# ORing_block.net
KiCad netlist of a schematic drawn in EAGLE
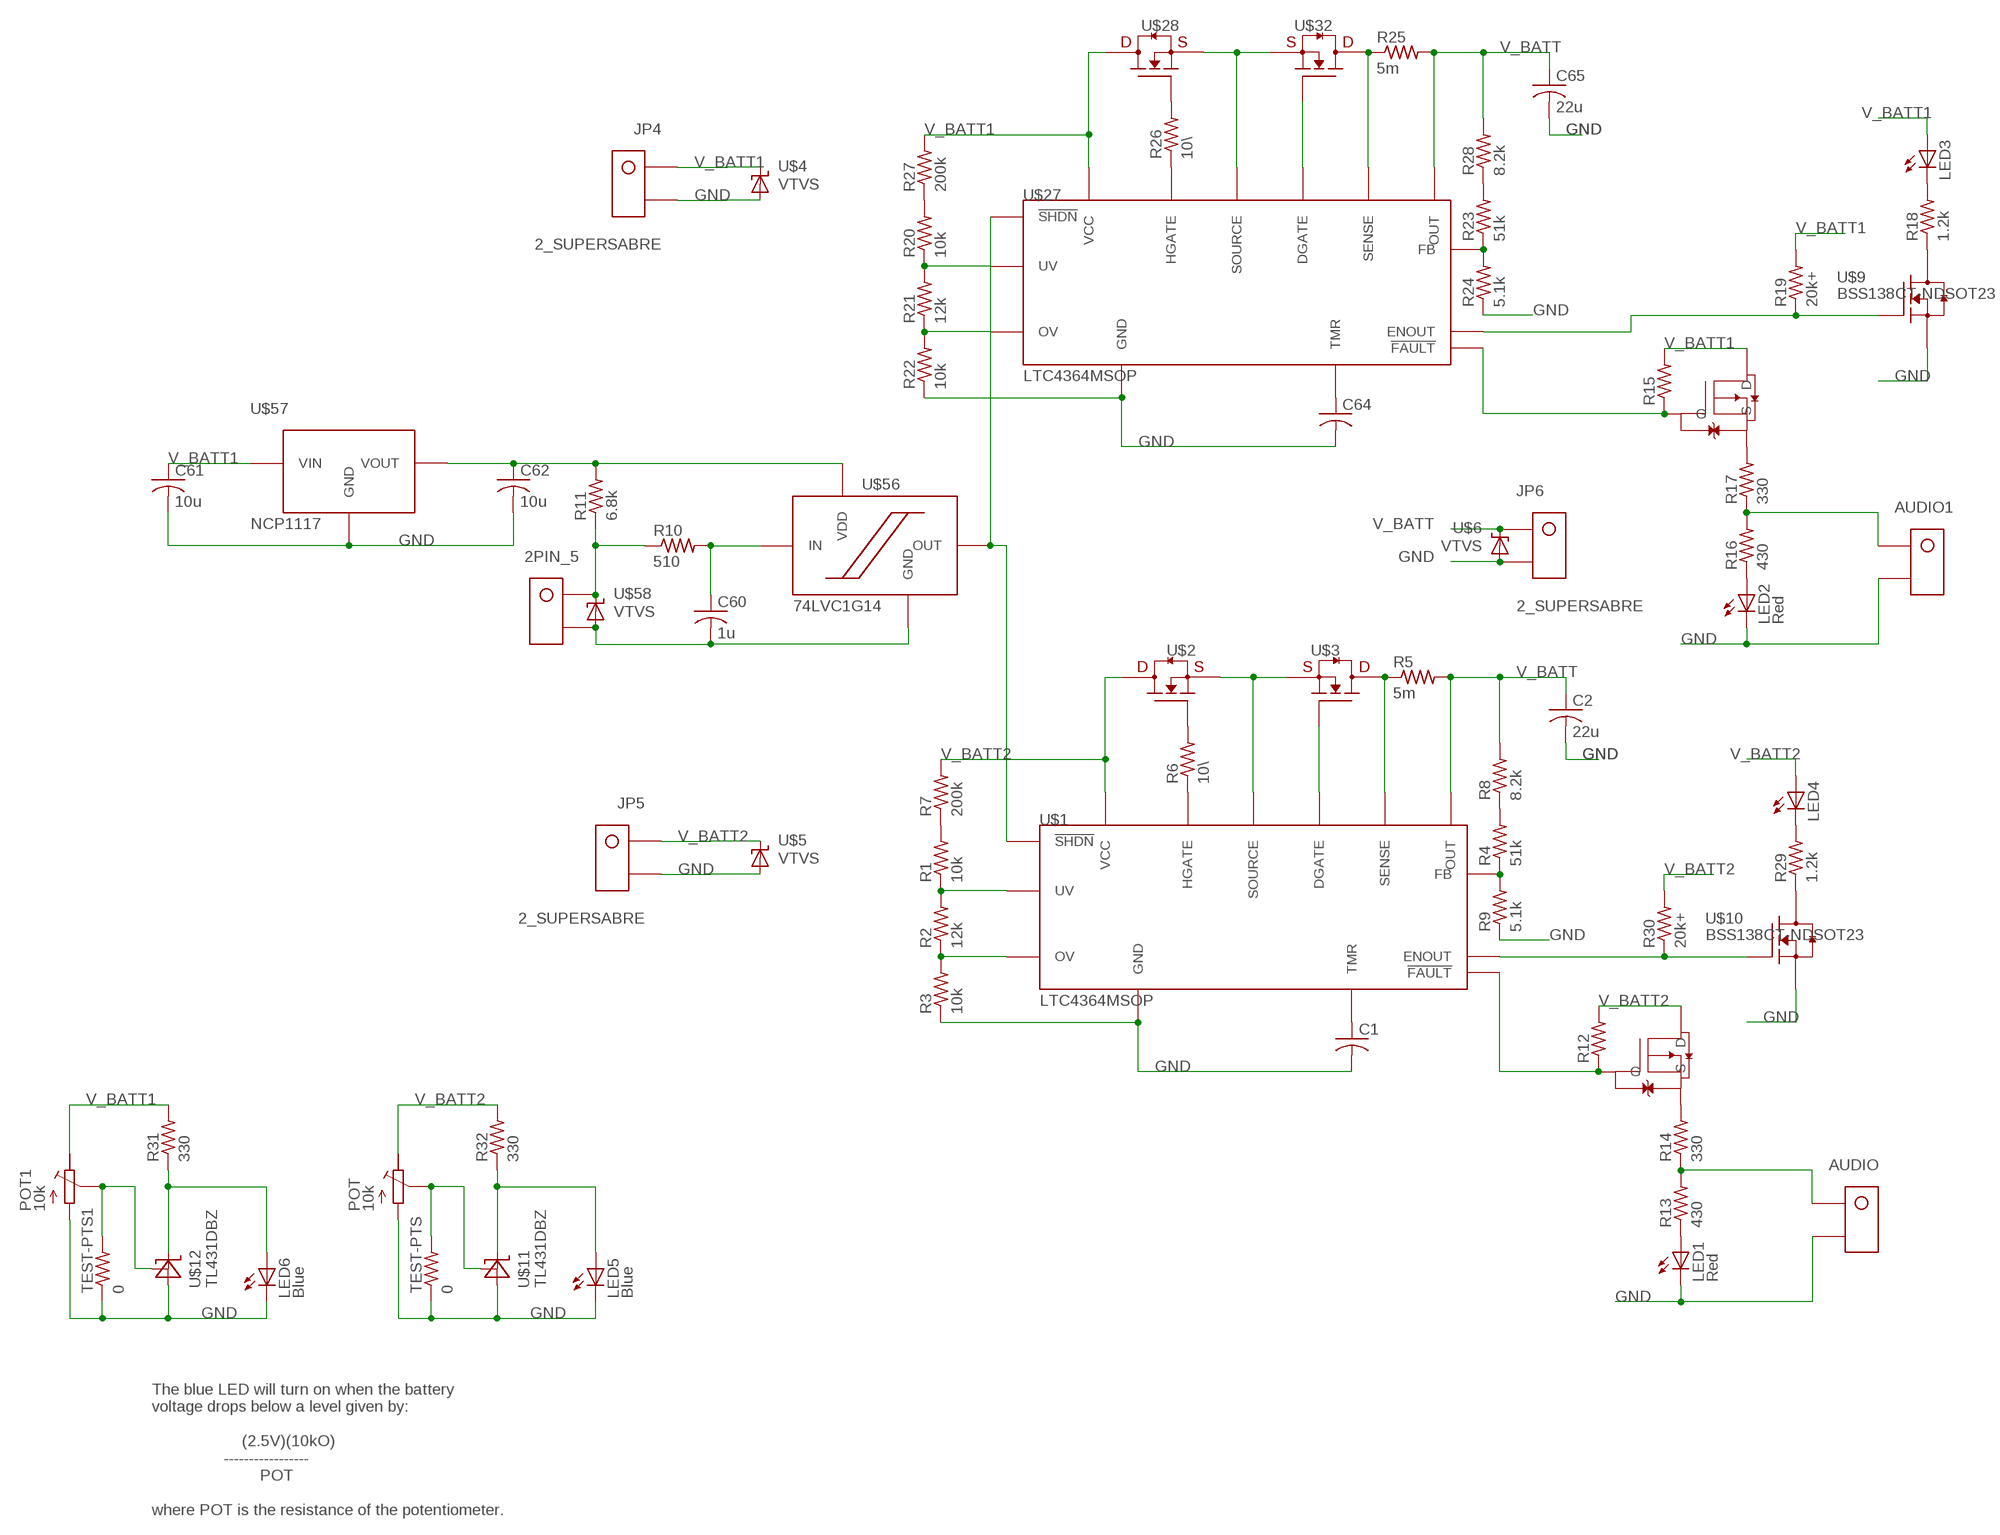
[diagram p0: schematic, sheet 1]

(export (version "E")
  (design (tool "Eeschema 10.0.6"))
  (components
    (comp (ref "2PIN_5")
      (value "KK254_VERT_2PIN22-29-2021")
      (footprint "eagle-import:KK254_VERT_2PIN")
      (libsource (lib "eagle-import") (part "KK254_VERT_2PIN22-29-2021"))
    )
    (comp (ref "AUDIO")
      (value "KK254_VERT_2PIN22-29-2021")
      (footprint "eagle-import:KK254_VERT_2PIN")
      (libsource (lib "eagle-import") (part "KK254_VERT_2PIN22-29-2021"))
    )
    (comp (ref "AUDIO1")
      (value "KK254_VERT_2PIN22-29-2021")
      (footprint "eagle-import:KK254_VERT_2PIN")
      (libsource (lib "eagle-import") (part "KK254_VERT_2PIN22-29-2021"))
    )
    (comp (ref "C1")
      (value "C-USC0805")
      (footprint "eagle-import:C0805")
      (libsource (lib "eagle-import") (part "C-USC0805"))
    )
    (comp (ref "C2")
      (value "22u")
      (footprint "eagle-import:C0805")
      (libsource (lib "eagle-import") (part "C-USC0805"))
    )
    (comp (ref "C60")
      (value "1u")
      (footprint "eagle-import:C0805")
      (libsource (lib "eagle-import") (part "C-USC0805"))
    )
    (comp (ref "C61")
      (value "10u")
      (footprint "eagle-import:C0805")
      (libsource (lib "eagle-import") (part "C-USC0805"))
    )
    (comp (ref "C62")
      (value "10u")
      (footprint "eagle-import:C0805")
      (libsource (lib "eagle-import") (part "C-USC0805"))
    )
    (comp (ref "C64")
      (value "C-USC0805")
      (footprint "eagle-import:C0805")
      (libsource (lib "eagle-import") (part "C-USC0805"))
    )
    (comp (ref "C65")
      (value "22u")
      (footprint "eagle-import:C0805")
      (libsource (lib "eagle-import") (part "C-USC0805"))
    )
    (comp (ref "JP4")
      (value "2_SUPERSABRE")
      (footprint "eagle-import:SUPERSABRE_2CIRCUIT")
      (libsource (lib "eagle-import") (part "2_SUPERSABRE"))
    )
    (comp (ref "JP5")
      (value "2_SUPERSABRE")
      (footprint "eagle-import:SUPERSABRE_2CIRCUIT")
      (libsource (lib "eagle-import") (part "2_SUPERSABRE"))
    )
    (comp (ref "JP6")
      (value "2_SUPERSABRE")
      (footprint "eagle-import:SUPERSABRE_2CIRCUIT")
      (libsource (lib "eagle-import") (part "2_SUPERSABRE"))
    )
    (comp (ref "LED1")
      (value "Red")
      (footprint "eagle-import:CHIPLED_0805")
      (libsource (lib "eagle-import") (part "LEDCHIPLED_0805"))
    )
    (comp (ref "LED2")
      (value "Red")
      (footprint "eagle-import:CHIPLED_0805")
      (libsource (lib "eagle-import") (part "LEDCHIPLED_0805"))
    )
    (comp (ref "LED3")
      (value "LEDCHIPLED_0805")
      (footprint "eagle-import:CHIPLED_0805")
      (libsource (lib "eagle-import") (part "LEDCHIPLED_0805"))
    )
    (comp (ref "LED4")
      (value "LEDCHIPLED_0805")
      (footprint "eagle-import:CHIPLED_0805")
      (libsource (lib "eagle-import") (part "LEDCHIPLED_0805"))
    )
    (comp (ref "LED5")
      (value "Blue")
      (footprint "eagle-import:0805")
      (libsource (lib "eagle-import") (part "0805_LED"))
    )
    (comp (ref "LED6")
      (value "Blue")
      (footprint "eagle-import:0805")
      (libsource (lib "eagle-import") (part "0805_LED"))
    )
    (comp (ref "POT")
      (value "10k")
      (footprint "eagle-import:PTV09A-4")
      (libsource (lib "eagle-import") (part "R-TRIMMPTV09A-4"))
    )
    (comp (ref "POT1")
      (value "10k")
      (footprint "eagle-import:PTV09A-4")
      (libsource (lib "eagle-import") (part "R-TRIMMPTV09A-4"))
    )
    (comp (ref "R1")
      (value "10k")
      (footprint "eagle-import:R0805")
      (libsource (lib "eagle-import") (part "R-US_R0805"))
    )
    (comp (ref "R2")
      (value "12k")
      (footprint "eagle-import:R0805")
      (libsource (lib "eagle-import") (part "R-US_R0805"))
    )
    (comp (ref "R3")
      (value "10k")
      (footprint "eagle-import:R0805")
      (libsource (lib "eagle-import") (part "R-US_R0805"))
    )
    (comp (ref "R4")
      (value "51k")
      (footprint "eagle-import:R0805")
      (libsource (lib "eagle-import") (part "R-US_R0805"))
    )
    (comp (ref "R5")
      (value "5m")
      (footprint "eagle-import:R0805")
      (libsource (lib "eagle-import") (part "R-US_R0805"))
    )
    (comp (ref "R6")
      (value "10\\")
      (footprint "eagle-import:R0805")
      (libsource (lib "eagle-import") (part "R-US_R0805"))
    )
    (comp (ref "R7")
      (value "200k")
      (footprint "eagle-import:R0805")
      (libsource (lib "eagle-import") (part "R-US_R0805"))
    )
    (comp (ref "R8")
      (value "8.2k")
      (footprint "eagle-import:R0805")
      (libsource (lib "eagle-import") (part "R-US_R0805"))
    )
    (comp (ref "R9")
      (value "5.1k")
      (footprint "eagle-import:R0805")
      (libsource (lib "eagle-import") (part "R-US_R0805"))
    )
    (comp (ref "R10")
      (value "510")
      (footprint "eagle-import:R0805")
      (libsource (lib "eagle-import") (part "R-US_R0805"))
    )
    (comp (ref "R11")
      (value "6.8k")
      (footprint "eagle-import:R0805")
      (libsource (lib "eagle-import") (part "R-US_R0805"))
    )
    (comp (ref "R12")
      (value "R-US_R0805")
      (footprint "eagle-import:R0805")
      (libsource (lib "eagle-import") (part "R-US_R0805"))
    )
    (comp (ref "R13")
      (value "430")
      (footprint "eagle-import:R0805")
      (libsource (lib "eagle-import") (part "R-US_R0805"))
    )
    (comp (ref "R14")
      (value "330")
      (footprint "eagle-import:R0805")
      (libsource (lib "eagle-import") (part "R-US_R0805"))
    )
    (comp (ref "R15")
      (value "R-US_R0805")
      (footprint "eagle-import:R0805")
      (libsource (lib "eagle-import") (part "R-US_R0805"))
    )
    (comp (ref "R16")
      (value "430")
      (footprint "eagle-import:R0805")
      (libsource (lib "eagle-import") (part "R-US_R0805"))
    )
    (comp (ref "R17")
      (value "330")
      (footprint "eagle-import:R0805")
      (libsource (lib "eagle-import") (part "R-US_R0805"))
    )
    (comp (ref "R18")
      (value "1.2k")
      (footprint "eagle-import:R0805")
      (libsource (lib "eagle-import") (part "R-US_R0805"))
    )
    (comp (ref "R19")
      (value "20k+")
      (footprint "eagle-import:R0805")
      (libsource (lib "eagle-import") (part "R-US_R0805"))
    )
    (comp (ref "R20")
      (value "10k")
      (footprint "eagle-import:R0805")
      (libsource (lib "eagle-import") (part "R-US_R0805"))
    )
    (comp (ref "R21")
      (value "12k")
      (footprint "eagle-import:R0805")
      (libsource (lib "eagle-import") (part "R-US_R0805"))
    )
    (comp (ref "R22")
      (value "10k")
      (footprint "eagle-import:R0805")
      (libsource (lib "eagle-import") (part "R-US_R0805"))
    )
    (comp (ref "R23")
      (value "51k")
      (footprint "eagle-import:R0805")
      (libsource (lib "eagle-import") (part "R-US_R0805"))
    )
    (comp (ref "R24")
      (value "5.1k")
      (footprint "eagle-import:R0805")
      (libsource (lib "eagle-import") (part "R-US_R0805"))
    )
    (comp (ref "R25")
      (value "5m")
      (footprint "eagle-import:R0805")
      (libsource (lib "eagle-import") (part "R-US_R0805"))
    )
    (comp (ref "R26")
      (value "10\\")
      (footprint "eagle-import:R0805")
      (libsource (lib "eagle-import") (part "R-US_R0805"))
    )
    (comp (ref "R27")
      (value "200k")
      (footprint "eagle-import:R0805")
      (libsource (lib "eagle-import") (part "R-US_R0805"))
    )
    (comp (ref "R28")
      (value "8.2k")
      (footprint "eagle-import:R0805")
      (libsource (lib "eagle-import") (part "R-US_R0805"))
    )
    (comp (ref "R29")
      (value "1.2k")
      (footprint "eagle-import:R0805")
      (libsource (lib "eagle-import") (part "R-US_R0805"))
    )
    (comp (ref "R30")
      (value "20k+")
      (footprint "eagle-import:R0805")
      (libsource (lib "eagle-import") (part "R-US_R0805"))
    )
    (comp (ref "R31")
      (value "330")
      (footprint "eagle-import:R0805")
      (libsource (lib "eagle-import") (part "R-US_R0805"))
    )
    (comp (ref "R32")
      (value "330")
      (footprint "eagle-import:R0805")
      (libsource (lib "eagle-import") (part "R-US_R0805"))
    )
    (comp (ref "TEST-PTS")
      (value "0")
      (footprint "eagle-import:V526-0")
      (libsource (lib "eagle-import") (part "R-US_V526-0"))
    )
    (comp (ref "TEST-PTS1")
      (value "0")
      (footprint "eagle-import:V526-0")
      (libsource (lib "eagle-import") (part "R-US_V526-0"))
    )
    (comp (ref "U$1")
      (value "LTC4364MSOP")
      (footprint "eagle-import:MSOP16")
      (libsource (lib "eagle-import") (part "LTC4364MSOP"))
    )
    (comp (ref "U$2")
      (value "FDMC8360LET40PWR33")
      (footprint "eagle-import:POWER33")
      (libsource (lib "eagle-import") (part "FDMC8360LET40PWR33"))
    )
    (comp (ref "U$3")
      (value "FDMC8360LET40PWR33")
      (footprint "eagle-import:POWER33")
      (libsource (lib "eagle-import") (part "FDMC8360LET40PWR33"))
    )
    (comp (ref "U$4")
      (value "VTVS")
      (footprint "eagle-import:DO-219AB")
      (libsource (lib "eagle-import") (part "VTVS"))
    )
    (comp (ref "U$5")
      (value "VTVS")
      (footprint "eagle-import:DO-219AB")
      (libsource (lib "eagle-import") (part "VTVS"))
    )
    (comp (ref "U$6")
      (value "VTVS")
      (footprint "eagle-import:DO-219AB")
      (libsource (lib "eagle-import") (part "VTVS"))
    )
    (comp (ref "U$7")
      (value "DMP32D5SFB")
      (footprint "eagle-import:AP02002")
      (libsource (lib "eagle-import") (part "DMP32D5SFB"))
    )
    (comp (ref "U$8")
      (value "DMP32D5SFB")
      (footprint "eagle-import:AP02002")
      (libsource (lib "eagle-import") (part "DMP32D5SFB"))
    )
    (comp (ref "U$9")
      (value "BSS138CT-NDSOT23")
      (footprint "eagle-import:SOT23")
      (libsource (lib "eagle-import") (part "BSS138CT-NDSOT23"))
    )
    (comp (ref "U$10")
      (value "BSS138CT-NDSOT23")
      (footprint "eagle-import:SOT23")
      (libsource (lib "eagle-import") (part "BSS138CT-NDSOT23"))
    )
    (comp (ref "U$11")
      (value "TL431DBZ")
      (footprint "eagle-import:SOT-23-3")
      (libsource (lib "eagle-import") (part "TL431DBZ"))
    )
    (comp (ref "U$12")
      (value "TL431DBZ")
      (footprint "eagle-import:SOT-23-3")
      (libsource (lib "eagle-import") (part "TL431DBZ"))
    )
    (comp (ref "U$27")
      (value "LTC4364MSOP")
      (footprint "eagle-import:MSOP16")
      (libsource (lib "eagle-import") (part "LTC4364MSOP"))
    )
    (comp (ref "U$28")
      (value "FDMC8360LET40PWR33")
      (footprint "eagle-import:POWER33")
      (libsource (lib "eagle-import") (part "FDMC8360LET40PWR33"))
    )
    (comp (ref "U$32")
      (value "FDMC8360LET40PWR33")
      (footprint "eagle-import:POWER33")
      (libsource (lib "eagle-import") (part "FDMC8360LET40PWR33"))
    )
    (comp (ref "U$56")
      (value "74LVC1G14")
      (footprint "eagle-import:TSSOP5")
      (libsource (lib "eagle-import") (part "74LVC1G14"))
    )
    (comp (ref "U$57")
      (value "NCP1117")
      (footprint "eagle-import:SOT-223")
      (libsource (lib "eagle-import") (part "NCP1117"))
    )
    (comp (ref "U$58")
      (value "VTVS")
      (footprint "eagle-import:DO-219AB")
      (libsource (lib "eagle-import") (part "VTVS"))
    )
  )
  (nets
    (net (code "1") (name "/GND") (class "Default")
      (node (ref "AUDIO") (pin "P$2") (pinfunction "P$2_P$2") (pintype "bidirectional"))
      (node (ref "AUDIO1") (pin "P$2") (pinfunction "P$2_P$2") (pintype "bidirectional"))
      (node (ref "C1") (pin "2") (pinfunction "2_2") (pintype "passive"))
      (node (ref "C2") (pin "2") (pinfunction "2_2") (pintype "passive"))
      (node (ref "C61") (pin "2") (pinfunction "2_2") (pintype "passive"))
      (node (ref "C62") (pin "2") (pinfunction "2_2") (pintype "passive"))
      (node (ref "C64") (pin "2") (pinfunction "2_2") (pintype "passive"))
      (node (ref "C65") (pin "2") (pinfunction "2_2") (pintype "passive"))
      (node (ref "JP4") (pin "P$2") (pinfunction "P$2_P$2") (pintype "bidirectional"))
      (node (ref "JP5") (pin "P$2") (pinfunction "P$2_P$2") (pintype "bidirectional"))
      (node (ref "JP6") (pin "P$2") (pinfunction "P$2_P$2") (pintype "bidirectional"))
      (node (ref "LED1") (pin "C") (pinfunction "C_C") (pintype "passive"))
      (node (ref "LED2") (pin "C") (pinfunction "C_C") (pintype "passive"))
      (node (ref "LED5") (pin "P$2") (pinfunction "C_P$2") (pintype "passive"))
      (node (ref "LED6") (pin "P$2") (pinfunction "C_P$2") (pintype "passive"))
      (node (ref "POT") (pin "P$3") (pinfunction "E_P$3") (pintype "passive"))
      (node (ref "POT1") (pin "P$3") (pinfunction "E_P$3") (pintype "passive"))
      (node (ref "R22") (pin "1") (pinfunction "1_1") (pintype "passive"))
      (node (ref "R24") (pin "1") (pinfunction "1_1") (pintype "passive"))
      (node (ref "R3") (pin "1") (pinfunction "1_1") (pintype "passive"))
      (node (ref "R9") (pin "1") (pinfunction "1_1") (pintype "passive"))
      (node (ref "TEST-PTS") (pin "1") (pinfunction "1_1") (pintype "passive"))
      (node (ref "TEST-PTS1") (pin "1") (pinfunction "1_1") (pintype "passive"))
      (node (ref "U$1") (pin "GND") (pinfunction "GND_GND") (pintype "bidirectional"))
      (node (ref "U$10") (pin "2") (pinfunction "S_2") (pintype "passive"))
      (node (ref "U$11") (pin "P$3") (pinfunction "A_P$3") (pintype "passive"))
      (node (ref "U$12") (pin "P$3") (pinfunction "A_P$3") (pintype "passive"))
      (node (ref "U$27") (pin "GND") (pinfunction "GND_GND") (pintype "bidirectional"))
      (node (ref "U$4") (pin "P$1") (pinfunction "A_P$1") (pintype "passive"))
      (node (ref "U$5") (pin "P$1") (pinfunction "A_P$1") (pintype "passive"))
      (node (ref "U$57") (pin "P$1") (pinfunction "GND_P$1") (pintype "bidirectional"))
      (node (ref "U$6") (pin "P$1") (pinfunction "A_P$1") (pintype "passive"))
      (node (ref "U$9") (pin "2") (pinfunction "S_2") (pintype "passive"))
    )
    (net (code "2") (name "/V_BATT") (class "Default")
      (node (ref "C2") (pin "1") (pinfunction "1_1") (pintype "passive"))
      (node (ref "C65") (pin "1") (pinfunction "1_1") (pintype "passive"))
      (node (ref "JP6") (pin "P$1") (pinfunction "P$1_P$1") (pintype "bidirectional"))
      (node (ref "R25") (pin "2") (pinfunction "2_2") (pintype "passive"))
      (node (ref "R28") (pin "2") (pinfunction "2_2") (pintype "passive"))
      (node (ref "R5") (pin "2") (pinfunction "2_2") (pintype "passive"))
      (node (ref "R8") (pin "2") (pinfunction "2_2") (pintype "passive"))
      (node (ref "U$1") (pin "OUT") (pinfunction "OUT_OUT") (pintype "bidirectional"))
      (node (ref "U$27") (pin "OUT") (pinfunction "OUT_OUT") (pintype "bidirectional"))
      (node (ref "U$6") (pin "P$2") (pinfunction "C_P$2") (pintype "passive"))
    )
    (net (code "3") (name "/V_BATT1") (class "Default")
      (node (ref "C61") (pin "1") (pinfunction "1_1") (pintype "passive"))
      (node (ref "JP4") (pin "P$1") (pinfunction "P$1_P$1") (pintype "bidirectional"))
      (node (ref "LED3") (pin "A") (pinfunction "A_A") (pintype "passive"))
      (node (ref "POT1") (pin "P$1") (pinfunction "A_P$1") (pintype "passive"))
      (node (ref "R15") (pin "2") (pinfunction "2_2") (pintype "passive"))
      (node (ref "R19") (pin "2") (pinfunction "2_2") (pintype "passive"))
      (node (ref "R27") (pin "2") (pinfunction "2_2") (pintype "passive"))
      (node (ref "R31") (pin "2") (pinfunction "2_2") (pintype "passive"))
      (node (ref "U$27") (pin "VCC") (pinfunction "VCC_VCC") (pintype "bidirectional"))
      (node (ref "U$28") (pin "DRAIN") (pinfunction "DRAIN_DRAIN") (pintype "bidirectional"))
      (node (ref "U$4") (pin "P$2") (pinfunction "C_P$2") (pintype "passive"))
      (node (ref "U$57") (pin "P$3") (pinfunction "VIN_P$3") (pintype "bidirectional"))
      (node (ref "U$8") (pin "P$3") (pinfunction "D_P$3") (pintype "bidirectional"))
    )
    (net (code "4") (name "/V_BATT2") (class "Default")
      (node (ref "JP5") (pin "P$1") (pinfunction "P$1_P$1") (pintype "bidirectional"))
      (node (ref "LED4") (pin "A") (pinfunction "A_A") (pintype "passive"))
      (node (ref "POT") (pin "P$1") (pinfunction "A_P$1") (pintype "passive"))
      (node (ref "R12") (pin "2") (pinfunction "2_2") (pintype "passive"))
      (node (ref "R30") (pin "2") (pinfunction "2_2") (pintype "passive"))
      (node (ref "R32") (pin "2") (pinfunction "2_2") (pintype "passive"))
      (node (ref "R7") (pin "2") (pinfunction "2_2") (pintype "passive"))
      (node (ref "U$1") (pin "VCC") (pinfunction "VCC_VCC") (pintype "bidirectional"))
      (node (ref "U$2") (pin "DRAIN") (pinfunction "DRAIN_DRAIN") (pintype "bidirectional"))
      (node (ref "U$5") (pin "P$2") (pinfunction "C_P$2") (pintype "passive"))
      (node (ref "U$7") (pin "P$3") (pinfunction "D_P$3") (pintype "bidirectional"))
    )
    (net (code "5") (name "Net-(AUDIO-PadP$1)") (class "Default")
      (node (ref "AUDIO") (pin "P$1") (pinfunction "P$1_P$1") (pintype "bidirectional"))
      (node (ref "R13") (pin "2") (pinfunction "2_2") (pintype "passive"))
      (node (ref "R14") (pin "1") (pinfunction "1_1") (pintype "passive"))
    )
    (net (code "6") (name "Net-(AUDIO1-PadP$1)") (class "Default")
      (node (ref "AUDIO1") (pin "P$1") (pinfunction "P$1_P$1") (pintype "bidirectional"))
      (node (ref "R16") (pin "2") (pinfunction "2_2") (pintype "passive"))
      (node (ref "R17") (pin "1") (pinfunction "1_1") (pintype "passive"))
    )
    (net (code "7") (name "Net-(C1-Pad1)") (class "Default")
      (node (ref "C1") (pin "1") (pinfunction "1_1") (pintype "passive"))
      (node (ref "U$1") (pin "TMR") (pinfunction "TMR_TMR") (pintype "bidirectional"))
    )
    (net (code "8") (name "Net-(C64-Pad1)") (class "Default")
      (node (ref "C64") (pin "1") (pinfunction "1_1") (pintype "passive"))
      (node (ref "U$27") (pin "TMR") (pinfunction "TMR_TMR") (pintype "bidirectional"))
    )
    (net (code "9") (name "Net-(LED1-PadA)") (class "Default")
      (node (ref "LED1") (pin "A") (pinfunction "A_A") (pintype "passive"))
      (node (ref "R13") (pin "1") (pinfunction "1_1") (pintype "passive"))
    )
    (net (code "10") (name "Net-(LED2-PadA)") (class "Default")
      (node (ref "LED2") (pin "A") (pinfunction "A_A") (pintype "passive"))
      (node (ref "R16") (pin "1") (pinfunction "1_1") (pintype "passive"))
    )
    (net (code "11") (name "Net-(LED3-PadC)") (class "Default")
      (node (ref "LED3") (pin "C") (pinfunction "C_C") (pintype "passive"))
      (node (ref "R18") (pin "2") (pinfunction "2_2") (pintype "passive"))
    )
    (net (code "12") (name "Net-(LED4-PadC)") (class "Default")
      (node (ref "LED4") (pin "C") (pinfunction "C_C") (pintype "passive"))
      (node (ref "R29") (pin "2") (pinfunction "2_2") (pintype "passive"))
    )
    (net (code "13") (name "Net-(LED5-A)") (class "Default")
      (node (ref "LED5") (pin "P$1") (pinfunction "A_P$1") (pintype "passive"))
      (node (ref "R32") (pin "1") (pinfunction "1_1") (pintype "passive"))
      (node (ref "U$11") (pin "P$1") (pinfunction "C_P$1") (pintype "passive"))
    )
    (net (code "14") (name "Net-(LED6-A)") (class "Default")
      (node (ref "LED6") (pin "P$1") (pinfunction "A_P$1") (pintype "passive"))
      (node (ref "R31") (pin "1") (pinfunction "1_1") (pintype "passive"))
      (node (ref "U$12") (pin "P$1") (pinfunction "C_P$1") (pintype "passive"))
    )
    (net (code "15") (name "Net-(POT-S)") (class "Default")
      (node (ref "POT") (pin "P$2") (pinfunction "S_P$2") (pintype "passive"))
      (node (ref "TEST-PTS") (pin "2") (pinfunction "2_2") (pintype "passive"))
      (node (ref "U$11") (pin "P$2") (pinfunction "REF_P$2") (pintype "bidirectional"))
    )
    (net (code "16") (name "Net-(POT1-S)") (class "Default")
      (node (ref "POT1") (pin "P$2") (pinfunction "S_P$2") (pintype "passive"))
      (node (ref "TEST-PTS1") (pin "2") (pinfunction "2_2") (pintype "passive"))
      (node (ref "U$12") (pin "P$2") (pinfunction "REF_P$2") (pintype "bidirectional"))
    )
    (net (code "17") (name "Net-(R1-Pad1)") (class "Default")
      (node (ref "R1") (pin "1") (pinfunction "1_1") (pintype "passive"))
      (node (ref "R2") (pin "2") (pinfunction "2_2") (pintype "passive"))
      (node (ref "U$1") (pin "UV") (pinfunction "UV_UV") (pintype "bidirectional"))
    )
    (net (code "18") (name "Net-(R1-Pad2)") (class "Default")
      (node (ref "R1") (pin "2") (pinfunction "2_2") (pintype "passive"))
      (node (ref "R7") (pin "1") (pinfunction "1_1") (pintype "passive"))
    )
    (net (code "19") (name "Net-(R2-Pad1)") (class "Default")
      (node (ref "R2") (pin "1") (pinfunction "1_1") (pintype "passive"))
      (node (ref "R3") (pin "2") (pinfunction "2_2") (pintype "passive"))
      (node (ref "U$1") (pin "OV") (pinfunction "OV_OV") (pintype "bidirectional"))
    )
    (net (code "20") (name "Net-(R4-Pad1)") (class "Default")
      (node (ref "R4") (pin "1") (pinfunction "1_1") (pintype "passive"))
      (node (ref "R9") (pin "2") (pinfunction "2_2") (pintype "passive"))
      (node (ref "U$1") (pin "FB") (pinfunction "FB_FB") (pintype "bidirectional"))
    )
    (net (code "21") (name "Net-(R4-Pad2)") (class "Default")
      (node (ref "R4") (pin "2") (pinfunction "2_2") (pintype "passive"))
      (node (ref "R8") (pin "1") (pinfunction "1_1") (pintype "passive"))
    )
    (net (code "22") (name "Net-(R5-Pad1)") (class "Default")
      (node (ref "R5") (pin "1") (pinfunction "1_1") (pintype "passive"))
      (node (ref "U$1") (pin "SENSE") (pinfunction "SENSE_SENSE") (pintype "bidirectional"))
      (node (ref "U$3") (pin "DRAIN") (pinfunction "DRAIN_DRAIN") (pintype "bidirectional"))
    )
    (net (code "23") (name "Net-(R6-Pad1)") (class "Default")
      (node (ref "R6") (pin "1") (pinfunction "1_1") (pintype "passive"))
      (node (ref "U$1") (pin "HGATE") (pinfunction "HGATE_HGATE") (pintype "bidirectional"))
    )
    (net (code "24") (name "Net-(R6-Pad2)") (class "Default")
      (node (ref "R6") (pin "2") (pinfunction "2_2") (pintype "passive"))
      (node (ref "U$2") (pin "GATE") (pinfunction "GATE_GATE") (pintype "passive"))
    )
    (net (code "25") (name "Net-(R20-Pad1)") (class "Default")
      (node (ref "R20") (pin "1") (pinfunction "1_1") (pintype "passive"))
      (node (ref "R21") (pin "2") (pinfunction "2_2") (pintype "passive"))
      (node (ref "U$27") (pin "UV") (pinfunction "UV_UV") (pintype "bidirectional"))
    )
    (net (code "26") (name "Net-(R20-Pad2)") (class "Default")
      (node (ref "R20") (pin "2") (pinfunction "2_2") (pintype "passive"))
      (node (ref "R27") (pin "1") (pinfunction "1_1") (pintype "passive"))
    )
    (net (code "27") (name "Net-(R21-Pad1)") (class "Default")
      (node (ref "R21") (pin "1") (pinfunction "1_1") (pintype "passive"))
      (node (ref "R22") (pin "2") (pinfunction "2_2") (pintype "passive"))
      (node (ref "U$27") (pin "OV") (pinfunction "OV_OV") (pintype "bidirectional"))
    )
    (net (code "28") (name "Net-(R23-Pad1)") (class "Default")
      (node (ref "R23") (pin "1") (pinfunction "1_1") (pintype "passive"))
      (node (ref "R24") (pin "2") (pinfunction "2_2") (pintype "passive"))
      (node (ref "U$27") (pin "FB") (pinfunction "FB_FB") (pintype "bidirectional"))
    )
    (net (code "29") (name "Net-(R23-Pad2)") (class "Default")
      (node (ref "R23") (pin "2") (pinfunction "2_2") (pintype "passive"))
      (node (ref "R28") (pin "1") (pinfunction "1_1") (pintype "passive"))
    )
    (net (code "30") (name "Net-(R25-Pad1)") (class "Default")
      (node (ref "R25") (pin "1") (pinfunction "1_1") (pintype "passive"))
      (node (ref "U$27") (pin "SENSE") (pinfunction "SENSE_SENSE") (pintype "bidirectional"))
      (node (ref "U$32") (pin "DRAIN") (pinfunction "DRAIN_DRAIN") (pintype "bidirectional"))
    )
    (net (code "31") (name "Net-(R26-Pad1)") (class "Default")
      (node (ref "R26") (pin "1") (pinfunction "1_1") (pintype "passive"))
      (node (ref "U$27") (pin "HGATE") (pinfunction "HGATE_HGATE") (pintype "bidirectional"))
    )
    (net (code "32") (name "Net-(R26-Pad2)") (class "Default")
      (node (ref "R26") (pin "2") (pinfunction "2_2") (pintype "passive"))
      (node (ref "U$28") (pin "GATE") (pinfunction "GATE_GATE") (pintype "passive"))
    )
    (net (code "33") (name "Net-(U$1-PadDGATE)") (class "Default")
      (node (ref "U$1") (pin "DGATE") (pinfunction "DGATE_DGATE") (pintype "bidirectional"))
      (node (ref "U$3") (pin "GATE") (pinfunction "GATE_GATE") (pintype "passive"))
    )
    (net (code "34") (name "Net-(U$1-PadSOURCE)") (class "Default")
      (node (ref "U$1") (pin "SOURCE") (pinfunction "SOURCE_SOURCE") (pintype "bidirectional"))
      (node (ref "U$2") (pin "SOURCE1") (pinfunction "SOURCE_SOURCE1") (pintype "passive"))
      (node (ref "U$2") (pin "SOURCE2") (pinfunction "SOURCE_SOURCE2") (pintype "passive"))
      (node (ref "U$2") (pin "SOURCE3") (pinfunction "SOURCE_SOURCE3") (pintype "passive"))
      (node (ref "U$3") (pin "SOURCE1") (pinfunction "SOURCE_SOURCE1") (pintype "passive"))
      (node (ref "U$3") (pin "SOURCE2") (pinfunction "SOURCE_SOURCE2") (pintype "passive"))
      (node (ref "U$3") (pin "SOURCE3") (pinfunction "SOURCE_SOURCE3") (pintype "passive"))
    )
    (net (code "35") (name "Net-(U$1-~{FAULT})") (class "Default")
      (node (ref "R12") (pin "1") (pinfunction "1_1") (pintype "passive"))
      (node (ref "U$1") (pin "FLT") (pinfunction "~{FAULT}_FLT") (pintype "bidirectional"))
      (node (ref "U$7") (pin "P$2") (pinfunction "G_P$2") (pintype "bidirectional"))
    )
    (net (code "36") (name "Net-(U$1-~{SHDN})") (class "Default")
      (node (ref "U$1") (pin "SHDN") (pinfunction "~{SHDN}_SHDN") (pintype "bidirectional"))
      (node (ref "U$27") (pin "SHDN") (pinfunction "~{SHDN}_SHDN") (pintype "bidirectional"))
      (node (ref "U$56") (pin "P$4") (pinfunction "OUT_P$4") (pintype "bidirectional"))
    )
    (net (code "37") (name "Net-(U$7-S)") (class "Default")
      (node (ref "R14") (pin "2") (pinfunction "2_2") (pintype "passive"))
      (node (ref "U$7") (pin "P$1") (pinfunction "S_P$1") (pintype "bidirectional"))
    )
    (net (code "38") (name "Net-(U$8-S)") (class "Default")
      (node (ref "R17") (pin "2") (pinfunction "2_2") (pintype "passive"))
      (node (ref "U$8") (pin "P$1") (pinfunction "S_P$1") (pintype "bidirectional"))
    )
    (net (code "39") (name "Net-(U$9-D)") (class "Default")
      (node (ref "R18") (pin "1") (pinfunction "1_1") (pintype "passive"))
      (node (ref "U$9") (pin "3") (pinfunction "D_3") (pintype "bidirectional"))
    )
    (net (code "40") (name "Net-(U$9-G)") (class "Default")
      (node (ref "R19") (pin "1") (pinfunction "1_1") (pintype "passive"))
      (node (ref "U$27") (pin "ENOUT") (pinfunction "ENOUT_ENOUT") (pintype "bidirectional"))
      (node (ref "U$9") (pin "1") (pinfunction "G_1") (pintype "passive"))
    )
    (net (code "41") (name "Net-(U$10-D)") (class "Default")
      (node (ref "R29") (pin "1") (pinfunction "1_1") (pintype "passive"))
      (node (ref "U$10") (pin "3") (pinfunction "D_3") (pintype "bidirectional"))
    )
    (net (code "42") (name "Net-(U$10-G)") (class "Default")
      (node (ref "R30") (pin "1") (pinfunction "1_1") (pintype "passive"))
      (node (ref "U$1") (pin "ENOUT") (pinfunction "ENOUT_ENOUT") (pintype "bidirectional"))
      (node (ref "U$10") (pin "1") (pinfunction "G_1") (pintype "passive"))
    )
    (net (code "43") (name "Net-(U$27-PadDGATE)") (class "Default")
      (node (ref "U$27") (pin "DGATE") (pinfunction "DGATE_DGATE") (pintype "bidirectional"))
      (node (ref "U$32") (pin "GATE") (pinfunction "GATE_GATE") (pintype "passive"))
    )
    (net (code "44") (name "Net-(U$27-PadSOURCE)") (class "Default")
      (node (ref "U$27") (pin "SOURCE") (pinfunction "SOURCE_SOURCE") (pintype "bidirectional"))
      (node (ref "U$28") (pin "SOURCE1") (pinfunction "SOURCE_SOURCE1") (pintype "passive"))
      (node (ref "U$28") (pin "SOURCE2") (pinfunction "SOURCE_SOURCE2") (pintype "passive"))
      (node (ref "U$28") (pin "SOURCE3") (pinfunction "SOURCE_SOURCE3") (pintype "passive"))
      (node (ref "U$32") (pin "SOURCE1") (pinfunction "SOURCE_SOURCE1") (pintype "passive"))
      (node (ref "U$32") (pin "SOURCE2") (pinfunction "SOURCE_SOURCE2") (pintype "passive"))
      (node (ref "U$32") (pin "SOURCE3") (pinfunction "SOURCE_SOURCE3") (pintype "passive"))
    )
    (net (code "45") (name "Net-(U$27-~{FAULT})") (class "Default")
      (node (ref "R15") (pin "1") (pinfunction "1_1") (pintype "passive"))
      (node (ref "U$27") (pin "FLT") (pinfunction "~{FAULT}_FLT") (pintype "bidirectional"))
      (node (ref "U$8") (pin "P$2") (pinfunction "G_P$2") (pintype "bidirectional"))
    )
    (net (code "46") (name "Net-(U$56-GND)") (class "Default")
      (node (ref "2PIN_5") (pin "P$2") (pinfunction "P$2_P$2") (pintype "bidirectional"))
      (node (ref "C60") (pin "2") (pinfunction "2_2") (pintype "passive"))
      (node (ref "U$56") (pin "P$3") (pinfunction "GND_P$3") (pintype "bidirectional"))
      (node (ref "U$58") (pin "P$1") (pinfunction "A_P$1") (pintype "passive"))
    )
    (net (code "47") (name "Net-(U$56-IN)") (class "Default")
      (node (ref "C60") (pin "1") (pinfunction "1_1") (pintype "passive"))
      (node (ref "R10") (pin "2") (pinfunction "2_2") (pintype "passive"))
      (node (ref "U$56") (pin "P$2") (pinfunction "IN_P$2") (pintype "bidirectional"))
    )
    (net (code "48") (name "Net-(U$56-VDD)") (class "Default")
      (node (ref "C62") (pin "1") (pinfunction "1_1") (pintype "passive"))
      (node (ref "R11") (pin "2") (pinfunction "2_2") (pintype "passive"))
      (node (ref "U$56") (pin "P$5") (pinfunction "VDD_P$5") (pintype "bidirectional"))
      (node (ref "U$57") (pin "P$2") (pinfunction "VOUT_P$2") (pintype "bidirectional"))
      (node (ref "U$57") (pin "P$4") (pinfunction "VOUT_P$4") (pintype "bidirectional"))
    )
    (net (code "49") (name "Net-(U$58-C)") (class "Default")
      (node (ref "2PIN_5") (pin "P$1") (pinfunction "P$1_P$1") (pintype "bidirectional"))
      (node (ref "R10") (pin "1") (pinfunction "1_1") (pintype "passive"))
      (node (ref "R11") (pin "1") (pinfunction "1_1") (pintype "passive"))
      (node (ref "U$58") (pin "P$2") (pinfunction "C_P$2") (pintype "passive"))
    )
  )
)
